# sensor.net
KiCad netlist of a schematic drawn in EAGLE
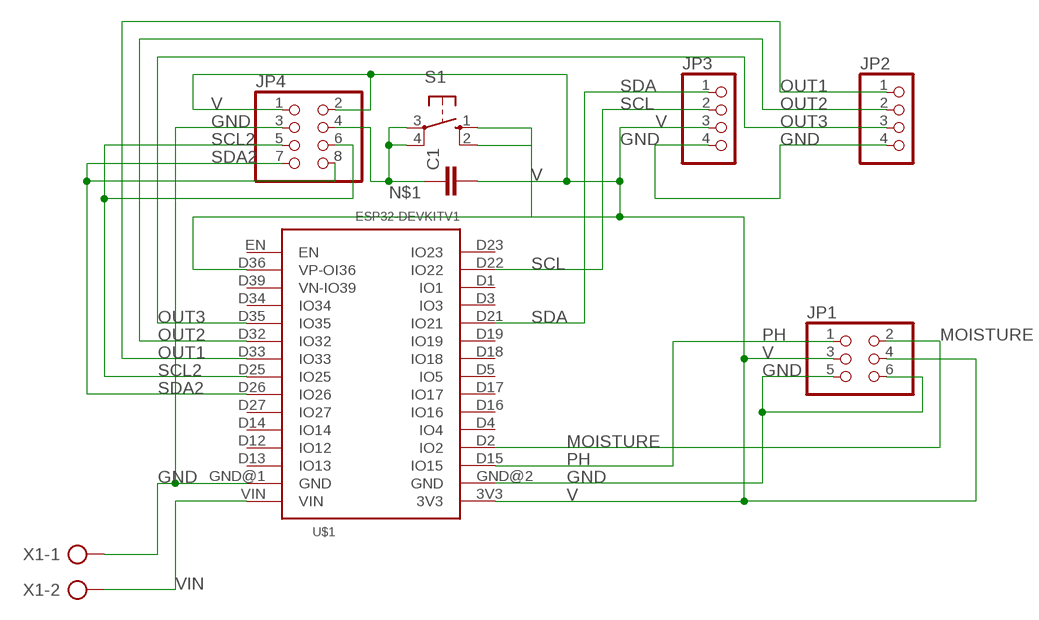
[diagram p0: schematic, sheet 1]

(export (version "E")
  (design (tool "Eeschema 10.0.6"))
  (components
    (comp (ref "C1")
      (value "C-EU050-030X075")
      (footprint "eagle-import:C050-030X075")
      (libsource (lib "eagle-import") (part "C-EU050-030X075"))
    )
    (comp (ref "JP1")
      (value "PINHD-2X3")
      (footprint "eagle-import:2X03")
      (libsource (lib "eagle-import") (part "PINHD-2X3"))
    )
    (comp (ref "JP2")
      (value "PINHD-1X4")
      (footprint "eagle-import:1X04")
      (libsource (lib "eagle-import") (part "PINHD-1X4"))
    )
    (comp (ref "JP3")
      (value "PINHD-1X4")
      (footprint "eagle-import:1X04")
      (libsource (lib "eagle-import") (part "PINHD-1X4"))
    )
    (comp (ref "JP4")
      (value "PINHD-2X4")
      (footprint "eagle-import:2X04")
      (libsource (lib "eagle-import") (part "PINHD-2X4"))
    )
    (comp (ref "S1")
      (value "10-XX")
      (footprint "eagle-import:B3F-10XX")
      (fields (field (name "MPN") "B3F-1000"))
      (libsource (lib "eagle-import") (part "10-XX"))
    )
    (comp (ref "U$1")
      (value "ESP32DEVKITV1")
      (footprint "eagle-import:ESP32-DEVKITV1")
      (libsource (lib "eagle-import") (part "ESP32DEVKITV1"))
    )
    (comp (ref "X1")
      (value "AK300/2")
      (footprint "eagle-import:AK300_2")
      (libsource (lib "eagle-import") (part "AK300/2"))
    )
  )
  (nets
    (net (code "1") (name "/GND") (class "Default")
      (node (ref "JP1") (pin "5") (pinfunction "5_5") (pintype "passive"))
      (node (ref "JP1") (pin "6") (pinfunction "6_6") (pintype "passive"))
      (node (ref "JP2") (pin "4") (pinfunction "4_4") (pintype "passive"))
      (node (ref "JP3") (pin "4") (pinfunction "4_4") (pintype "passive"))
      (node (ref "JP4") (pin "3") (pinfunction "3_3") (pintype "passive"))
      (node (ref "U$1") (pin "GND@1") (pinfunction "GND_GND@1") (pintype "bidirectional"))
      (node (ref "U$1") (pin "GND@2") (pinfunction "GND_GND@2") (pintype "bidirectional"))
      (node (ref "X1") (pin "1") (pinfunction "KL_1") (pintype "passive"))
    )
    (net (code "2") (name "/MOISTURE") (class "Default")
      (node (ref "JP1") (pin "2") (pinfunction "2_2") (pintype "passive"))
      (node (ref "U$1") (pin "D2") (pinfunction "IO2_D2") (pintype "bidirectional"))
    )
    (net (code "3") (name "/N$1") (class "Default")
      (node (ref "C1") (pin "1") (pinfunction "1_1") (pintype "passive"))
      (node (ref "JP4") (pin "4") (pinfunction "4_4") (pintype "passive"))
      (node (ref "S1") (pin "3") (pinfunction "P_3") (pintype "passive"))
      (node (ref "S1") (pin "4") (pinfunction "P1_4") (pintype "passive"))
    )
    (net (code "4") (name "/OUT1") (class "Default")
      (node (ref "JP2") (pin "1") (pinfunction "1_1") (pintype "passive"))
      (node (ref "U$1") (pin "D33") (pinfunction "IO33_D33") (pintype "bidirectional"))
    )
    (net (code "5") (name "/OUT2") (class "Default")
      (node (ref "JP2") (pin "2") (pinfunction "2_2") (pintype "passive"))
      (node (ref "U$1") (pin "D32") (pinfunction "IO32_D32") (pintype "bidirectional"))
    )
    (net (code "6") (name "/OUT3") (class "Default")
      (node (ref "JP2") (pin "3") (pinfunction "3_3") (pintype "passive"))
      (node (ref "U$1") (pin "D35") (pinfunction "IO35_D35") (pintype "bidirectional"))
    )
    (net (code "7") (name "/PH") (class "Default")
      (node (ref "JP1") (pin "1") (pinfunction "1_1") (pintype "passive"))
      (node (ref "U$1") (pin "D15") (pinfunction "IO15_D15") (pintype "bidirectional"))
    )
    (net (code "8") (name "/SCL") (class "Default")
      (node (ref "JP3") (pin "2") (pinfunction "2_2") (pintype "passive"))
      (node (ref "U$1") (pin "D22") (pinfunction "IO22_D22") (pintype "bidirectional"))
    )
    (net (code "9") (name "/SCL2") (class "Default")
      (node (ref "JP4") (pin "5") (pinfunction "5_5") (pintype "passive"))
      (node (ref "JP4") (pin "6") (pinfunction "6_6") (pintype "passive"))
      (node (ref "U$1") (pin "D25") (pinfunction "IO25_D25") (pintype "bidirectional"))
    )
    (net (code "10") (name "/SDA") (class "Default")
      (node (ref "JP3") (pin "1") (pinfunction "1_1") (pintype "passive"))
      (node (ref "U$1") (pin "D21") (pinfunction "IO21_D21") (pintype "bidirectional"))
    )
    (net (code "11") (name "/SDA2") (class "Default")
      (node (ref "JP4") (pin "7") (pinfunction "7_7") (pintype "passive"))
      (node (ref "JP4") (pin "8") (pinfunction "8_8") (pintype "passive"))
      (node (ref "U$1") (pin "D26") (pinfunction "IO26_D26") (pintype "bidirectional"))
    )
    (net (code "12") (name "/V") (class "Default")
      (node (ref "C1") (pin "2") (pinfunction "2_2") (pintype "passive"))
      (node (ref "JP1") (pin "3") (pinfunction "3_3") (pintype "passive"))
      (node (ref "JP1") (pin "4") (pinfunction "4_4") (pintype "passive"))
      (node (ref "JP3") (pin "3") (pinfunction "3_3") (pintype "passive"))
      (node (ref "JP4") (pin "1") (pinfunction "1_1") (pintype "passive"))
      (node (ref "JP4") (pin "2") (pinfunction "2_2") (pintype "passive"))
      (node (ref "S1") (pin "1") (pinfunction "S_1") (pintype "passive"))
      (node (ref "S1") (pin "2") (pinfunction "S1_2") (pintype "passive"))
      (node (ref "U$1") (pin "3V3") (pinfunction "3V3_3V3") (pintype "bidirectional"))
      (node (ref "U$1") (pin "D36") (pinfunction "VP-OI36_D36") (pintype "bidirectional"))
    )
    (net (code "13") (name "/VIN") (class "Default")
      (node (ref "U$1") (pin "VIN") (pinfunction "VIN_VIN") (pintype "bidirectional"))
      (node (ref "X1") (pin "2") (pinfunction "KL_2") (pintype "passive"))
    )
    (net (code "14") (name "unconnected-(U$1-IO1-PadD1)") (class "Default")
      (node (ref "U$1") (pin "D1") (pinfunction "IO1_D1") (pintype "bidirectional"))
    )
    (net (code "15") (name "unconnected-(U$1-IO3-PadD3)") (class "Default")
      (node (ref "U$1") (pin "D3") (pinfunction "IO3_D3") (pintype "bidirectional"))
    )
    (net (code "16") (name "unconnected-(U$1-IO4-PadD4)") (class "Default")
      (node (ref "U$1") (pin "D4") (pinfunction "IO4_D4") (pintype "bidirectional"))
    )
    (net (code "17") (name "unconnected-(U$1-IO5-PadD5)") (class "Default")
      (node (ref "U$1") (pin "D5") (pinfunction "IO5_D5") (pintype "bidirectional"))
    )
    (net (code "18") (name "unconnected-(U$1-IO12-PadD12)") (class "Default")
      (node (ref "U$1") (pin "D12") (pinfunction "IO12_D12") (pintype "bidirectional"))
    )
    (net (code "19") (name "unconnected-(U$1-IO13-PadD13)") (class "Default")
      (node (ref "U$1") (pin "D13") (pinfunction "IO13_D13") (pintype "bidirectional"))
    )
    (net (code "20") (name "unconnected-(U$1-IO14-PadD14)") (class "Default")
      (node (ref "U$1") (pin "D14") (pinfunction "IO14_D14") (pintype "bidirectional"))
    )
    (net (code "21") (name "unconnected-(U$1-IO16-PadD16)") (class "Default")
      (node (ref "U$1") (pin "D16") (pinfunction "IO16_D16") (pintype "bidirectional"))
    )
    (net (code "22") (name "unconnected-(U$1-IO17-PadD17)") (class "Default")
      (node (ref "U$1") (pin "D17") (pinfunction "IO17_D17") (pintype "bidirectional"))
    )
    (net (code "23") (name "unconnected-(U$1-IO18-PadD18)") (class "Default")
      (node (ref "U$1") (pin "D18") (pinfunction "IO18_D18") (pintype "bidirectional"))
    )
    (net (code "24") (name "unconnected-(U$1-IO19-PadD19)") (class "Default")
      (node (ref "U$1") (pin "D19") (pinfunction "IO19_D19") (pintype "bidirectional"))
    )
    (net (code "25") (name "unconnected-(U$1-IO23-PadD23)") (class "Default")
      (node (ref "U$1") (pin "D23") (pinfunction "IO23_D23") (pintype "bidirectional"))
    )
    (net (code "26") (name "unconnected-(U$1-IO27-PadD27)") (class "Default")
      (node (ref "U$1") (pin "D27") (pinfunction "IO27_D27") (pintype "bidirectional"))
    )
    (net (code "27") (name "unconnected-(U$1-IO34-PadD34)") (class "Default")
      (node (ref "U$1") (pin "D34") (pinfunction "IO34_D34") (pintype "bidirectional"))
    )
    (net (code "28") (name "unconnected-(U$1-PadEN)") (class "Default")
      (node (ref "U$1") (pin "EN") (pinfunction "EN_EN") (pintype "bidirectional"))
    )
    (net (code "29") (name "unconnected-(U$1-VN-IO39-PadD39)") (class "Default")
      (node (ref "U$1") (pin "D39") (pinfunction "VN-IO39_D39") (pintype "bidirectional"))
    )
  )
)
